# oa_sevenfortyfun.net
KiCad netlist of a schematic drawn in EAGLE
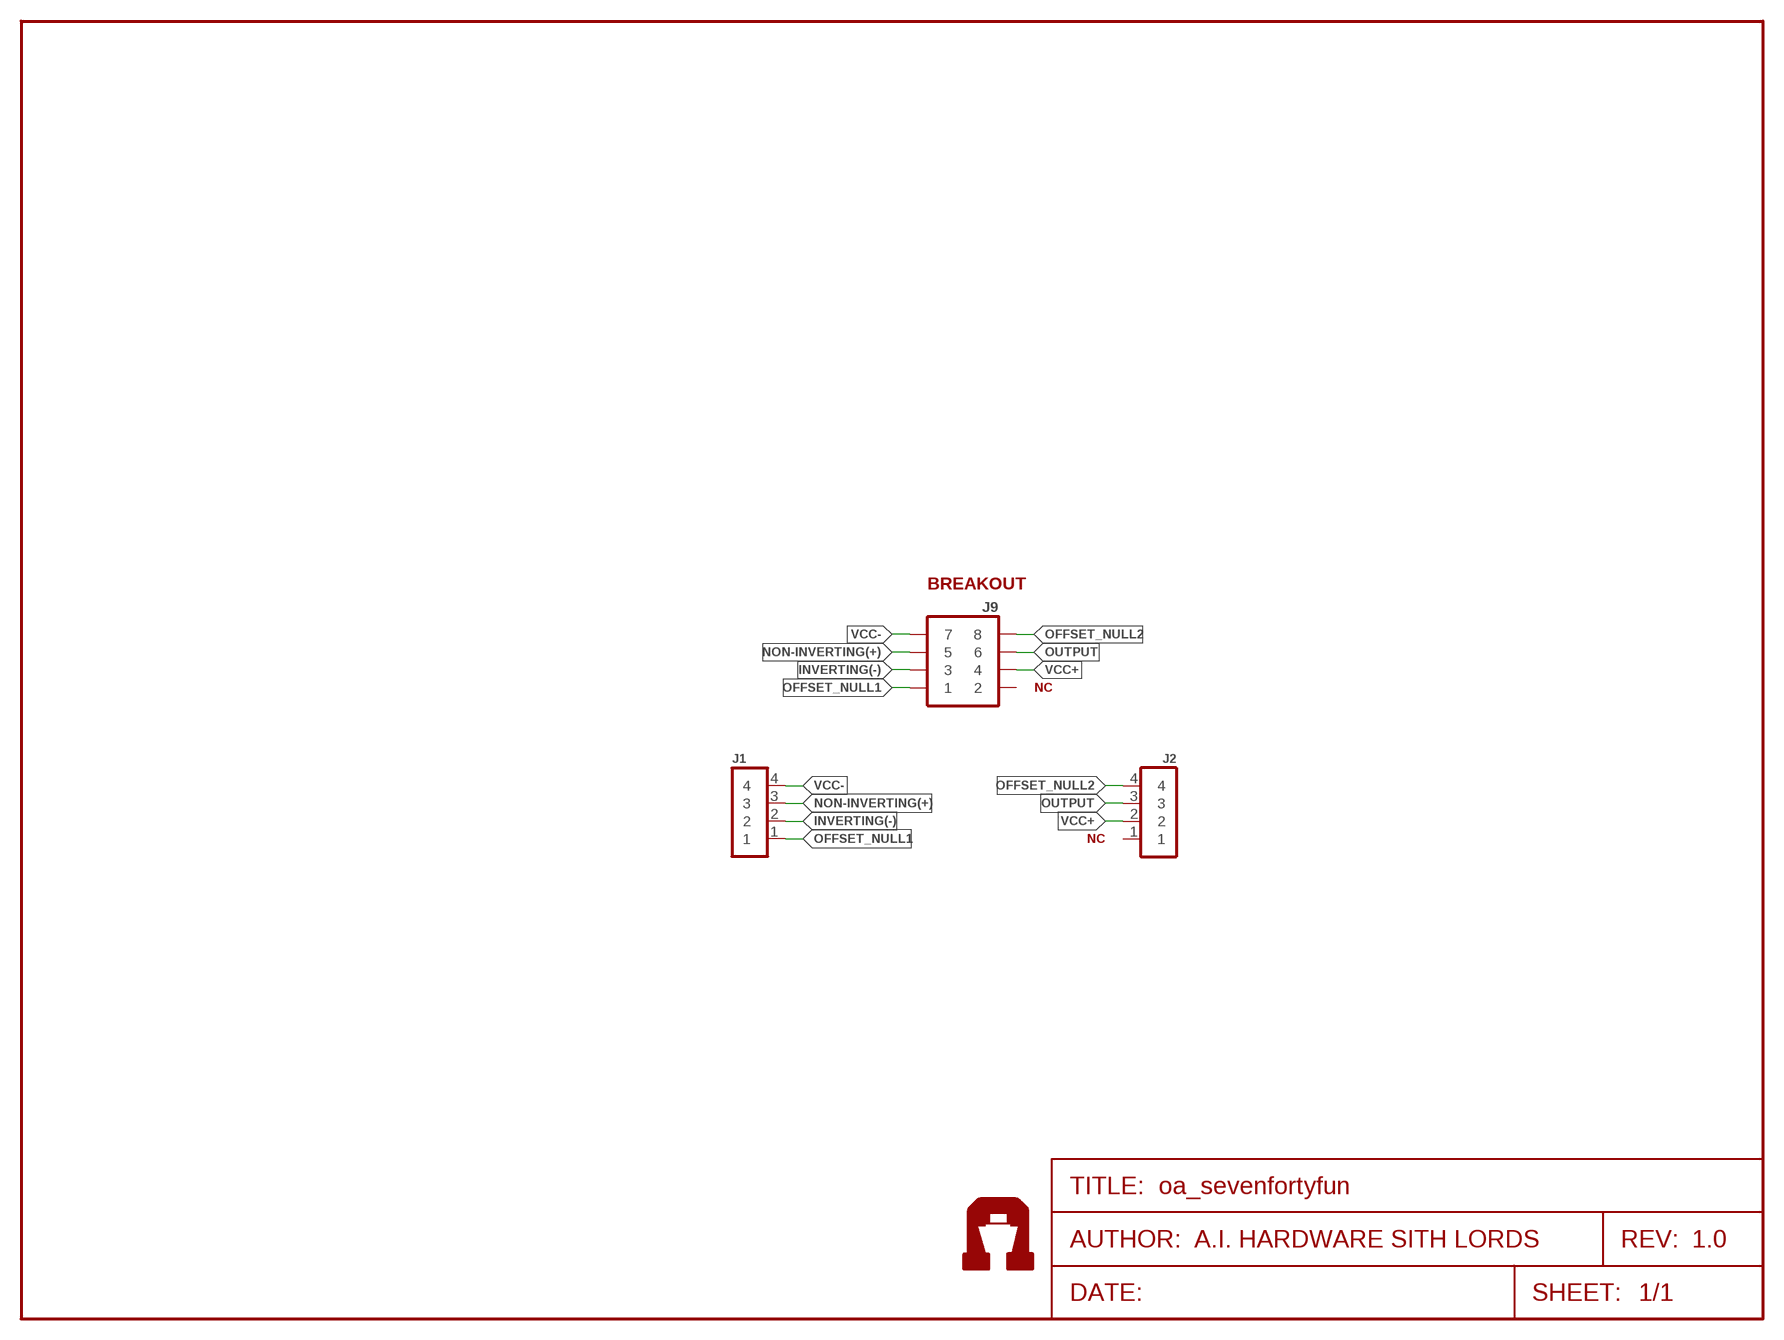
[diagram p0: schematic, sheet 1]

(export (version "E")
  (design (tool "Eeschema 10.0.6"))
  (components
    (comp (ref "J1")
      (value "1X04NOSILK")
      (footprint "eagle-import:1X04-NOSILK")
      (libsource (lib "eagle-import") (part "1X04NOSILK"))
    )
    (comp (ref "J2")
      (value "1X04NOFIRST")
      (footprint "eagle-import:1X04-NOFIRST")
      (libsource (lib "eagle-import") (part "1X04NOFIRST"))
    )
    (comp (ref "J9")
      (value "2X04SHR")
      (footprint "eagle-import:2X04-SHR")
      (libsource (lib "eagle-import") (part "2X04SHR"))
    )
    (comp (ref "U$3")
      (value "AI-LOGOXS")
      (footprint "eagle-import:AI-LOGO-XS")
      (libsource (lib "eagle-import") (part "AI-LOGOXS"))
    )
  )
  (nets
    (net (code "1") (name "INVERTING(-)") (class "Default")
      (node (ref "J1") (pin "2") (pinfunction "2_2") (pintype "bidirectional"))
      (node (ref "J9") (pin "3") (pinfunction "3_3") (pintype "bidirectional"))
    )
    (net (code "2") (name "NON-INVERTING(+)") (class "Default")
      (node (ref "J1") (pin "3") (pinfunction "3_3") (pintype "bidirectional"))
      (node (ref "J9") (pin "5") (pinfunction "5_5") (pintype "bidirectional"))
    )
    (net (code "3") (name "OFFSET_NULL1") (class "Default")
      (node (ref "J1") (pin "1") (pinfunction "1_1") (pintype "bidirectional"))
      (node (ref "J9") (pin "1") (pinfunction "1_1") (pintype "bidirectional"))
    )
    (net (code "4") (name "OFFSET_NULL2") (class "Default")
      (node (ref "J2") (pin "4") (pinfunction "4_4") (pintype "bidirectional"))
      (node (ref "J9") (pin "8") (pinfunction "8_8") (pintype "bidirectional"))
    )
    (net (code "5") (name "OUTPUT") (class "Default")
      (node (ref "J2") (pin "3") (pinfunction "3_3") (pintype "bidirectional"))
      (node (ref "J9") (pin "6") (pinfunction "6_6") (pintype "bidirectional"))
    )
    (net (code "6") (name "VCC+") (class "Default")
      (node (ref "J2") (pin "2") (pinfunction "2_2") (pintype "bidirectional"))
      (node (ref "J9") (pin "4") (pinfunction "4_4") (pintype "bidirectional"))
    )
    (net (code "7") (name "VCC-") (class "Default")
      (node (ref "J1") (pin "4") (pinfunction "4_4") (pintype "bidirectional"))
      (node (ref "J9") (pin "7") (pinfunction "7_7") (pintype "bidirectional"))
    )
    (net (code "8") (name "unconnected-(J2-Pad1)") (class "Default")
      (node (ref "J2") (pin "1") (pinfunction "1_1") (pintype "bidirectional"))
    )
    (net (code "9") (name "unconnected-(J9-Pad2)") (class "Default")
      (node (ref "J9") (pin "2") (pinfunction "2_2") (pintype "bidirectional"))
    )
  )
)
